# GTM_SPIconnector.net
KiCad netlist of a schematic drawn in Altium Designer
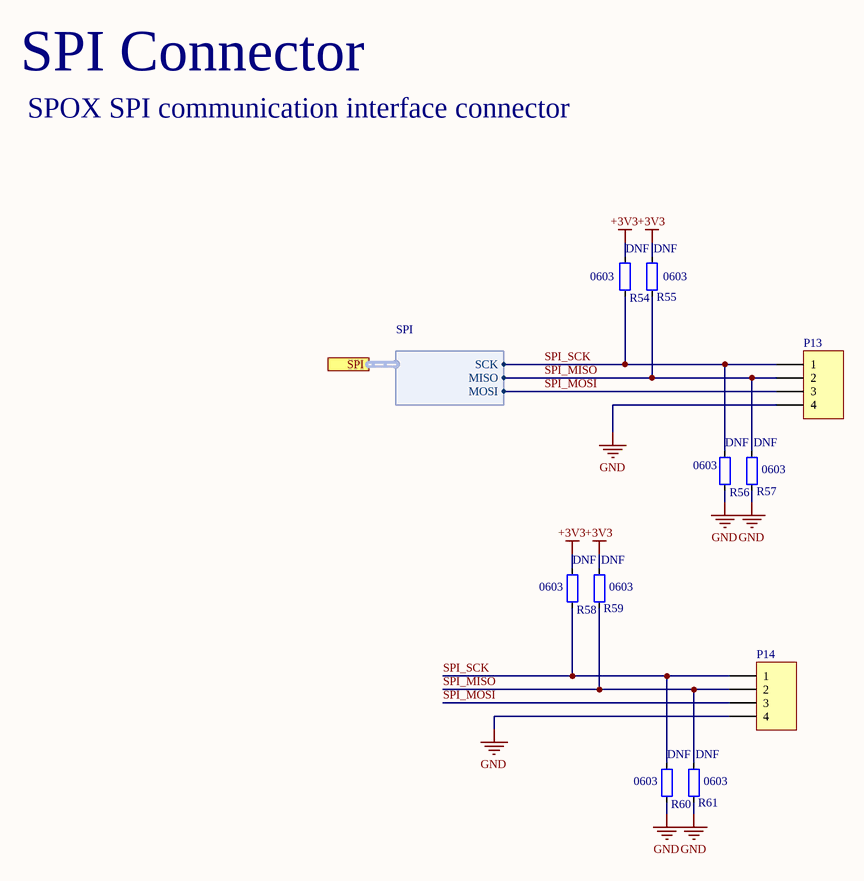
[diagram p0: GTM_SPIconnector.SchDoc]

(export (version "E")
  (design (tool "Eeschema 10.0.6"))
  (components
    (comp (ref "P13")
      (value "HDR1X4")
      (footprint "Molex SPOX Angle 4 Circuits")
      (description "Header, 4-Pin")
      (fields (field (name "PUBLISHER") "Altium Limited"))
      (libsource (lib "Library_Altium_KNR") (part "HDR1X4"))
    )
    (comp (ref "P14")
      (value "HDR1X4")
      (footprint "Molex SPOX Angle 4 Circuits")
      (description "Doubled SPI Connector")
      (fields (field (name "PUBLISHER") "Altium Limited"))
      (libsource (lib "Library_Altium_KNR") (part "HDR1X4"))
    )
    (comp (ref "R54")
      (value "DNF")
      (footprint "0603")
      (description "Resistior")
      (fields (field (name "PACKAGE") "0603"))
      (libsource (lib "Library_Altium_KNR") (part "RES"))
    )
    (comp (ref "R55")
      (value "DNF")
      (footprint "0603")
      (description "Resistior")
      (fields (field (name "PACKAGE") "0603"))
      (libsource (lib "Library_Altium_KNR") (part "RES"))
    )
    (comp (ref "R56")
      (value "DNF")
      (footprint "0603")
      (description "Resistior")
      (fields (field (name "PACKAGE") "0603"))
      (libsource (lib "Library_Altium_KNR") (part "RES"))
    )
    (comp (ref "R57")
      (value "DNF")
      (footprint "0603")
      (description "Resistior")
      (fields (field (name "PACKAGE") "0603"))
      (libsource (lib "Library_Altium_KNR") (part "RES"))
    )
    (comp (ref "R58")
      (value "DNF")
      (footprint "0603")
      (description "Resistior")
      (fields (field (name "PACKAGE") "0603"))
      (libsource (lib "Library_Altium_KNR") (part "RES"))
    )
    (comp (ref "R59")
      (value "DNF")
      (footprint "0603")
      (description "Resistior")
      (fields (field (name "PACKAGE") "0603"))
      (libsource (lib "Library_Altium_KNR") (part "RES"))
    )
    (comp (ref "R60")
      (value "DNF")
      (footprint "0603")
      (description "Resistior")
      (fields (field (name "PACKAGE") "0603"))
      (libsource (lib "Library_Altium_KNR") (part "RES"))
    )
    (comp (ref "R61")
      (value "DNF")
      (footprint "0603")
      (description "Resistior")
      (fields (field (name "PACKAGE") "0603"))
      (libsource (lib "Library_Altium_KNR") (part "RES"))
    )
  )
  (nets
    (net (code "2") (name "+3V3") (class "Default")
      (node (ref "R54") (pin "2") (pinfunction "2_2") (pintype "passive"))
      (node (ref "R55") (pin "2") (pinfunction "2_2") (pintype "passive"))
      (node (ref "R58") (pin "2") (pinfunction "2_2") (pintype "passive"))
      (node (ref "R59") (pin "2") (pinfunction "2_2") (pintype "passive"))
    )
    (net (code "3") (name "/SPI_MISO") (class "Default")
      (node (ref "P13") (pin "2") (pinfunction "2_2") (pintype "passive"))
      (node (ref "P14") (pin "2") (pinfunction "2_2") (pintype "passive"))
      (node (ref "R55") (pin "1") (pinfunction "1_1") (pintype "passive"))
      (node (ref "R57") (pin "2") (pinfunction "2_2") (pintype "passive"))
      (node (ref "R59") (pin "1") (pinfunction "1_1") (pintype "passive"))
      (node (ref "R61") (pin "2") (pinfunction "2_2") (pintype "passive"))
    )
    (net (code "4") (name "/SPI_MOSI") (class "Default")
      (node (ref "P13") (pin "3") (pinfunction "3_3") (pintype "passive"))
      (node (ref "P14") (pin "3") (pinfunction "3_3") (pintype "passive"))
    )
    (net (code "5") (name "/SPI_SCK") (class "Default")
      (node (ref "P13") (pin "1") (pinfunction "1_1") (pintype "passive"))
      (node (ref "P14") (pin "1") (pinfunction "1_1") (pintype "passive"))
      (node (ref "R54") (pin "1") (pinfunction "1_1") (pintype "passive"))
      (node (ref "R56") (pin "2") (pinfunction "2_2") (pintype "passive"))
      (node (ref "R58") (pin "1") (pinfunction "1_1") (pintype "passive"))
      (node (ref "R60") (pin "2") (pinfunction "2_2") (pintype "passive"))
    )
    (net (code "7") (name "GND") (class "Default")
      (node (ref "P13") (pin "4") (pinfunction "4_4") (pintype "passive"))
      (node (ref "P14") (pin "4") (pinfunction "4_4") (pintype "passive"))
      (node (ref "R56") (pin "1") (pinfunction "1_1") (pintype "passive"))
      (node (ref "R57") (pin "1") (pinfunction "1_1") (pintype "passive"))
      (node (ref "R60") (pin "1") (pinfunction "1_1") (pintype "passive"))
      (node (ref "R61") (pin "1") (pinfunction "1_1") (pintype "passive"))
    )
  )
)
